# mother4.net
KiCad netlist of a schematic drawn in EAGLE
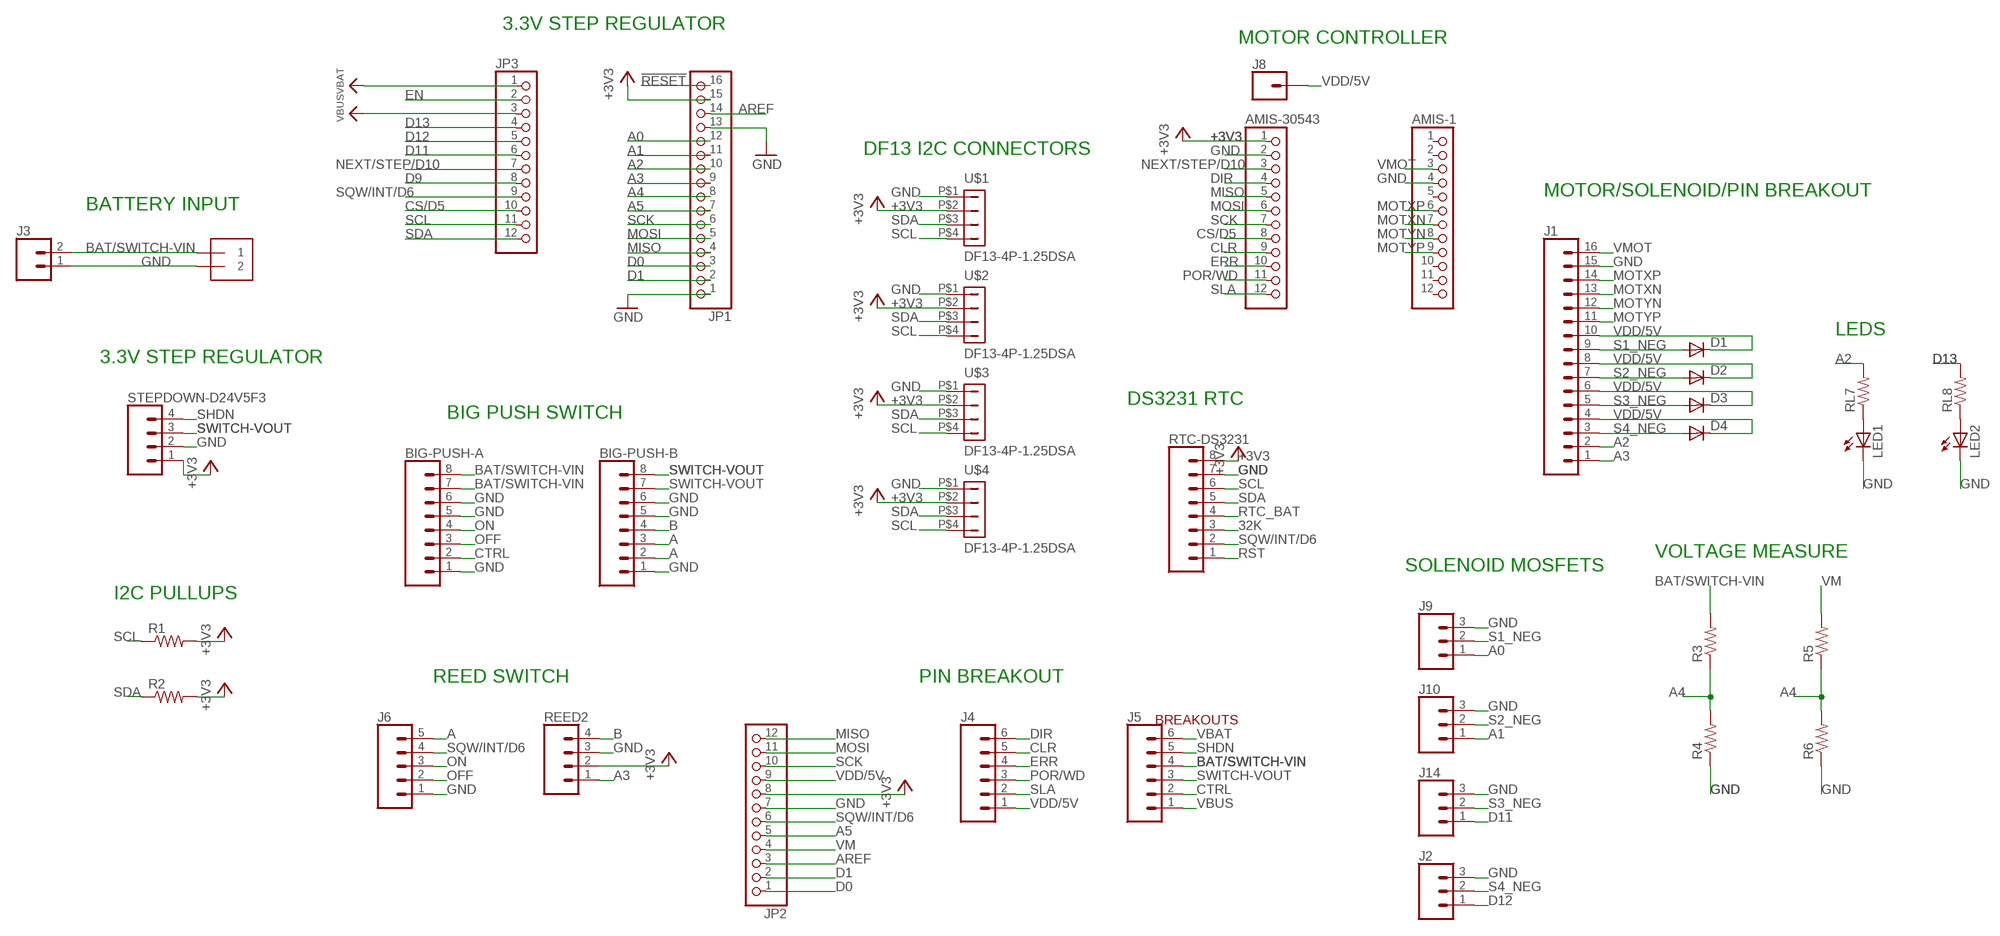
[diagram p0: schematic, sheet 1]

(export (version "E")
  (design (tool "Eeschema 10.0.6"))
  (components
    (comp (ref "AMIS-1")
      (value "PINHD-1X12-CB")
      (footprint "eagle-import:1X12-CB")
      (libsource (lib "eagle-import") (part "PINHD-1X12-CB"))
    )
    (comp (ref "AMIS-30543")
      (value "PINHD-1X12-CB")
      (footprint "eagle-import:1X12-CB")
      (libsource (lib "eagle-import") (part "PINHD-1X12-CB"))
    )
    (comp (ref "BAT")
      (value "1X2-3.5MM")
      (footprint "eagle-import:1X2-3.5MM")
      (libsource (lib "eagle-import") (part "1X2-3.5MM"))
    )
    (comp (ref "BIG-PUSH-A")
      (value "CONN_08\"")
      (footprint "eagle-import:1X08")
      (libsource (lib "eagle-import") (part "CONN_08{dblquote}"))
    )
    (comp (ref "BIG-PUSH-B")
      (value "CONN_08\"")
      (footprint "eagle-import:1X08")
      (libsource (lib "eagle-import") (part "CONN_08{dblquote}"))
    )
    (comp (ref "D1")
      (value "1N4148DO35-7")
      (footprint "eagle-import:DO35-7")
      (libsource (lib "eagle-import") (part "1N4148DO35-7"))
    )
    (comp (ref "D2")
      (value "1N4148DO35-7")
      (footprint "eagle-import:DO35-7")
      (libsource (lib "eagle-import") (part "1N4148DO35-7"))
    )
    (comp (ref "D3")
      (value "1N4148DO35-7")
      (footprint "eagle-import:DO35-7")
      (libsource (lib "eagle-import") (part "1N4148DO35-7"))
    )
    (comp (ref "D4")
      (value "1N4148DO35-7")
      (footprint "eagle-import:DO35-7")
      (libsource (lib "eagle-import") (part "1N4148DO35-7"))
    )
    (comp (ref "J1")
      (value "CONN_16")
      (footprint "eagle-import:1X16")
      (libsource (lib "eagle-import") (part "CONN_16"))
    )
    (comp (ref "J2")
      (value "CONN_03")
      (footprint "eagle-import:1X03")
      (libsource (lib "eagle-import") (part "CONN_03"))
    )
    (comp (ref "J3")
      (value "CONN_02")
      (footprint "eagle-import:1X02")
      (libsource (lib "eagle-import") (part "CONN_02"))
    )
    (comp (ref "J4")
      (value "CONN_06SILK_FEMALE_PTH")
      (footprint "eagle-import:1X06")
      (libsource (lib "eagle-import") (part "CONN_06SILK_FEMALE_PTH"))
    )
    (comp (ref "J5")
      (value "CONN_06SILK_FEMALE_PTH")
      (footprint "eagle-import:1X06")
      (libsource (lib "eagle-import") (part "CONN_06SILK_FEMALE_PTH"))
    )
    (comp (ref "J6")
      (value "CONN_05")
      (footprint "eagle-import:1X05")
      (libsource (lib "eagle-import") (part "CONN_05"))
    )
    (comp (ref "J8")
      (value "CONN_01")
      (footprint "eagle-import:1X01")
      (libsource (lib "eagle-import") (part "CONN_01"))
    )
    (comp (ref "J9")
      (value "CONN_03")
      (footprint "eagle-import:1X03")
      (libsource (lib "eagle-import") (part "CONN_03"))
    )
    (comp (ref "J10")
      (value "CONN_03")
      (footprint "eagle-import:1X03")
      (libsource (lib "eagle-import") (part "CONN_03"))
    )
    (comp (ref "J14")
      (value "CONN_03")
      (footprint "eagle-import:1X03")
      (libsource (lib "eagle-import") (part "CONN_03"))
    )
    (comp (ref "JP1")
      (value "HEADER-1X16ROUND")
      (footprint "eagle-import:1X16_ROUND")
      (libsource (lib "eagle-import") (part "HEADER-1X16ROUND"))
    )
    (comp (ref "JP2")
      (value "HEADER-1X12")
      (footprint "eagle-import:1X12_ROUND")
      (libsource (lib "eagle-import") (part "HEADER-1X12"))
    )
    (comp (ref "JP3")
      (value "HEADER-1X12")
      (footprint "eagle-import:1X12_ROUND")
      (libsource (lib "eagle-import") (part "HEADER-1X12"))
    )
    (comp (ref "LED1")
      (value "LED5MM")
      (footprint "eagle-import:LED5MM")
      (libsource (lib "eagle-import") (part "LED5MM"))
    )
    (comp (ref "LED2")
      (value "LED5MM")
      (footprint "eagle-import:LED5MM")
      (libsource (lib "eagle-import") (part "LED5MM"))
    )
    (comp (ref "R1")
      (value "R-US_0207/10")
      (footprint "eagle-import:0207_10")
      (libsource (lib "eagle-import") (part "R-US_0207/10"))
    )
    (comp (ref "R2")
      (value "R-US_0207/10")
      (footprint "eagle-import:0207_10")
      (libsource (lib "eagle-import") (part "R-US_0207/10"))
    )
    (comp (ref "R3")
      (value "R-US_0207/10")
      (footprint "eagle-import:0207_10")
      (libsource (lib "eagle-import") (part "R-US_0207/10"))
    )
    (comp (ref "R4")
      (value "R-US_0207/10")
      (footprint "eagle-import:0207_10")
      (libsource (lib "eagle-import") (part "R-US_0207/10"))
    )
    (comp (ref "R5")
      (value "R-US_0207/10")
      (footprint "eagle-import:0207_10")
      (libsource (lib "eagle-import") (part "R-US_0207/10"))
    )
    (comp (ref "R6")
      (value "R-US_0207/10")
      (footprint "eagle-import:0207_10")
      (libsource (lib "eagle-import") (part "R-US_0207/10"))
    )
    (comp (ref "REED2")
      (value "CONN_04")
      (footprint "eagle-import:1X04")
      (libsource (lib "eagle-import") (part "CONN_04"))
    )
    (comp (ref "RL7")
      (value "R-US_0207/10")
      (footprint "eagle-import:0207_10")
      (libsource (lib "eagle-import") (part "R-US_0207/10"))
    )
    (comp (ref "RL8")
      (value "R-US_0207/10")
      (footprint "eagle-import:0207_10")
      (libsource (lib "eagle-import") (part "R-US_0207/10"))
    )
    (comp (ref "RTC-DS3231")
      (value "CONN_08\"")
      (footprint "eagle-import:1X08")
      (libsource (lib "eagle-import") (part "CONN_08{dblquote}"))
    )
    (comp (ref "STEPDOWN-D24V5F3")
      (value "CONN_04")
      (footprint "eagle-import:1X04")
      (libsource (lib "eagle-import") (part "CONN_04"))
    )
    (comp (ref "U$1")
      (value "DF13-4P-1.25DSA")
      (footprint "eagle-import:DF13-4P-1.25DSA")
      (libsource (lib "eagle-import") (part "DF13-4P-1.25DSA"))
    )
    (comp (ref "U$2")
      (value "DF13-4P-1.25DSA")
      (footprint "eagle-import:DF13-4P-1.25DSA")
      (libsource (lib "eagle-import") (part "DF13-4P-1.25DSA"))
    )
    (comp (ref "U$3")
      (value "DF13-4P-1.25DSA")
      (footprint "eagle-import:DF13-4P-1.25DSA")
      (libsource (lib "eagle-import") (part "DF13-4P-1.25DSA"))
    )
    (comp (ref "U$4")
      (value "DF13-4P-1.25DSA")
      (footprint "eagle-import:DF13-4P-1.25DSA")
      (libsource (lib "eagle-import") (part "DF13-4P-1.25DSA"))
    )
  )
  (nets
    (net (code "1") (name "+3V3") (class "Default")
      (node (ref "AMIS-30543") (pin "1") (pinfunction "1_1") (pintype "passive"))
      (node (ref "JP1") (pin "15") (pinfunction "15_15") (pintype "passive"))
      (node (ref "JP2") (pin "8") (pinfunction "8_8") (pintype "passive"))
      (node (ref "R1") (pin "2") (pinfunction "2_2") (pintype "passive"))
      (node (ref "R2") (pin "2") (pinfunction "2_2") (pintype "passive"))
      (node (ref "REED2") (pin "2") (pinfunction "2_2") (pintype "passive"))
      (node (ref "RTC-DS3231") (pin "8") (pinfunction "8_8") (pintype "passive"))
      (node (ref "STEPDOWN-D24V5F3") (pin "1") (pinfunction "1_1") (pintype "passive"))
      (node (ref "U$1") (pin "P$2") (pinfunction "2_P$2") (pintype "passive"))
      (node (ref "U$2") (pin "P$2") (pinfunction "2_P$2") (pintype "passive"))
      (node (ref "U$3") (pin "P$2") (pinfunction "2_P$2") (pintype "passive"))
      (node (ref "U$4") (pin "P$2") (pinfunction "2_P$2") (pintype "passive"))
    )
    (net (code "2") (name "/32K") (class "Default")
      (node (ref "RTC-DS3231") (pin "3") (pinfunction "3_3") (pintype "passive"))
    )
    (net (code "3") (name "/A") (class "Default")
      (node (ref "BIG-PUSH-B") (pin "2") (pinfunction "2_2") (pintype "passive"))
      (node (ref "BIG-PUSH-B") (pin "3") (pinfunction "3_3") (pintype "passive"))
      (node (ref "J6") (pin "5") (pinfunction "5_5") (pintype "passive"))
    )
    (net (code "4") (name "/A0") (class "Default")
      (node (ref "J9") (pin "1") (pinfunction "1_1") (pintype "passive"))
      (node (ref "JP1") (pin "12") (pinfunction "12_12") (pintype "passive"))
    )
    (net (code "5") (name "/A1") (class "Default")
      (node (ref "J10") (pin "1") (pinfunction "1_1") (pintype "passive"))
      (node (ref "JP1") (pin "11") (pinfunction "11_11") (pintype "passive"))
    )
    (net (code "6") (name "/A2") (class "Default")
      (node (ref "J1") (pin "2") (pinfunction "2_2") (pintype "passive"))
      (node (ref "JP1") (pin "10") (pinfunction "10_10") (pintype "passive"))
      (node (ref "RL7") (pin "2") (pinfunction "2_2") (pintype "passive"))
    )
    (net (code "7") (name "/A3") (class "Default")
      (node (ref "J1") (pin "1") (pinfunction "1_1") (pintype "passive"))
      (node (ref "JP1") (pin "9") (pinfunction "9_9") (pintype "passive"))
      (node (ref "REED2") (pin "1") (pinfunction "1_1") (pintype "passive"))
    )
    (net (code "8") (name "/A4") (class "Default")
      (node (ref "JP1") (pin "8") (pinfunction "8_8") (pintype "passive"))
      (node (ref "R3") (pin "1") (pinfunction "1_1") (pintype "passive"))
      (node (ref "R4") (pin "2") (pinfunction "2_2") (pintype "passive"))
      (node (ref "R5") (pin "1") (pinfunction "1_1") (pintype "passive"))
      (node (ref "R6") (pin "2") (pinfunction "2_2") (pintype "passive"))
    )
    (net (code "9") (name "/A5") (class "Default")
      (node (ref "JP1") (pin "7") (pinfunction "7_7") (pintype "passive"))
      (node (ref "JP2") (pin "5") (pinfunction "5_5") (pintype "passive"))
    )
    (net (code "10") (name "/AREF") (class "Default")
      (node (ref "JP1") (pin "14") (pinfunction "14_14") (pintype "passive"))
      (node (ref "JP2") (pin "3") (pinfunction "3_3") (pintype "passive"))
    )
    (net (code "11") (name "/B") (class "Default")
      (node (ref "BIG-PUSH-B") (pin "4") (pinfunction "4_4") (pintype "passive"))
      (node (ref "REED2") (pin "4") (pinfunction "4_4") (pintype "passive"))
    )
    (net (code "12") (name "/BAT{slash}SWITCH-VIN") (class "Default")
      (node (ref "BAT") (pin "1") (pinfunction "1_1") (pintype "passive"))
      (node (ref "BIG-PUSH-A") (pin "7") (pinfunction "7_7") (pintype "passive"))
      (node (ref "BIG-PUSH-A") (pin "8") (pinfunction "8_8") (pintype "passive"))
      (node (ref "J3") (pin "2") (pinfunction "2_2") (pintype "passive"))
      (node (ref "J5") (pin "4") (pinfunction "4_4") (pintype "passive"))
      (node (ref "R3") (pin "2") (pinfunction "2_2") (pintype "passive"))
    )
    (net (code "13") (name "/CLR") (class "Default")
      (node (ref "AMIS-30543") (pin "9") (pinfunction "9_9") (pintype "passive"))
      (node (ref "J4") (pin "5") (pinfunction "5_5") (pintype "passive"))
    )
    (net (code "14") (name "/CS{slash}D5") (class "Default")
      (node (ref "AMIS-30543") (pin "8") (pinfunction "8_8") (pintype "passive"))
      (node (ref "JP3") (pin "10") (pinfunction "10_10") (pintype "passive"))
    )
    (net (code "15") (name "/CTRL") (class "Default")
      (node (ref "BIG-PUSH-A") (pin "2") (pinfunction "2_2") (pintype "passive"))
      (node (ref "J5") (pin "2") (pinfunction "2_2") (pintype "passive"))
    )
    (net (code "16") (name "/D0") (class "Default")
      (node (ref "JP1") (pin "3") (pinfunction "3_3") (pintype "passive"))
      (node (ref "JP2") (pin "1") (pinfunction "1_1") (pintype "passive"))
    )
    (net (code "17") (name "/D1") (class "Default")
      (node (ref "JP1") (pin "2") (pinfunction "2_2") (pintype "passive"))
      (node (ref "JP2") (pin "2") (pinfunction "2_2") (pintype "passive"))
    )
    (net (code "18") (name "/D9") (class "Default")
      (node (ref "JP3") (pin "8") (pinfunction "8_8") (pintype "passive"))
    )
    (net (code "19") (name "/D11") (class "Default")
      (node (ref "J14") (pin "1") (pinfunction "1_1") (pintype "passive"))
      (node (ref "JP3") (pin "6") (pinfunction "6_6") (pintype "passive"))
    )
    (net (code "20") (name "/D12") (class "Default")
      (node (ref "J2") (pin "1") (pinfunction "1_1") (pintype "passive"))
      (node (ref "JP3") (pin "5") (pinfunction "5_5") (pintype "passive"))
    )
    (net (code "21") (name "/D13") (class "Default")
      (node (ref "JP3") (pin "4") (pinfunction "4_4") (pintype "passive"))
      (node (ref "RL8") (pin "2") (pinfunction "2_2") (pintype "passive"))
    )
    (net (code "22") (name "/DIR") (class "Default")
      (node (ref "AMIS-30543") (pin "4") (pinfunction "4_4") (pintype "passive"))
      (node (ref "J4") (pin "6") (pinfunction "6_6") (pintype "passive"))
    )
    (net (code "23") (name "/EN") (class "Default")
      (node (ref "JP3") (pin "2") (pinfunction "2_2") (pintype "passive"))
    )
    (net (code "24") (name "/ERR") (class "Default")
      (node (ref "AMIS-30543") (pin "10") (pinfunction "10_10") (pintype "passive"))
      (node (ref "J4") (pin "4") (pinfunction "4_4") (pintype "passive"))
    )
    (net (code "25") (name "/MISO") (class "Default")
      (node (ref "AMIS-30543") (pin "5") (pinfunction "5_5") (pintype "passive"))
      (node (ref "JP1") (pin "4") (pinfunction "4_4") (pintype "passive"))
      (node (ref "JP2") (pin "12") (pinfunction "12_12") (pintype "passive"))
    )
    (net (code "26") (name "/MOSI") (class "Default")
      (node (ref "AMIS-30543") (pin "6") (pinfunction "6_6") (pintype "passive"))
      (node (ref "JP1") (pin "5") (pinfunction "5_5") (pintype "passive"))
      (node (ref "JP2") (pin "11") (pinfunction "11_11") (pintype "passive"))
    )
    (net (code "27") (name "/MOTXN") (class "Default")
      (node (ref "AMIS-1") (pin "7") (pinfunction "7_7") (pintype "passive"))
      (node (ref "J1") (pin "13") (pinfunction "13_13") (pintype "passive"))
    )
    (net (code "28") (name "/MOTXP") (class "Default")
      (node (ref "AMIS-1") (pin "6") (pinfunction "6_6") (pintype "passive"))
      (node (ref "J1") (pin "14") (pinfunction "14_14") (pintype "passive"))
    )
    (net (code "29") (name "/MOTYN") (class "Default")
      (node (ref "AMIS-1") (pin "8") (pinfunction "8_8") (pintype "passive"))
      (node (ref "J1") (pin "12") (pinfunction "12_12") (pintype "passive"))
    )
    (net (code "30") (name "/MOTYP") (class "Default")
      (node (ref "AMIS-1") (pin "9") (pinfunction "9_9") (pintype "passive"))
      (node (ref "J1") (pin "11") (pinfunction "11_11") (pintype "passive"))
    )
    (net (code "31") (name "/NEXT{slash}STEP{slash}D10") (class "Default")
      (node (ref "AMIS-30543") (pin "3") (pinfunction "3_3") (pintype "passive"))
      (node (ref "JP3") (pin "7") (pinfunction "7_7") (pintype "passive"))
    )
    (net (code "32") (name "/OFF") (class "Default")
      (node (ref "BIG-PUSH-A") (pin "3") (pinfunction "3_3") (pintype "passive"))
      (node (ref "J6") (pin "2") (pinfunction "2_2") (pintype "passive"))
    )
    (net (code "33") (name "/ON") (class "Default")
      (node (ref "BIG-PUSH-A") (pin "4") (pinfunction "4_4") (pintype "passive"))
      (node (ref "J6") (pin "3") (pinfunction "3_3") (pintype "passive"))
    )
    (net (code "34") (name "/POR{slash}WD") (class "Default")
      (node (ref "AMIS-30543") (pin "11") (pinfunction "11_11") (pintype "passive"))
      (node (ref "J4") (pin "3") (pinfunction "3_3") (pintype "passive"))
    )
    (net (code "35") (name "/RST") (class "Default")
      (node (ref "RTC-DS3231") (pin "1") (pinfunction "1_1") (pintype "passive"))
    )
    (net (code "36") (name "/RTC_BAT") (class "Default")
      (node (ref "RTC-DS3231") (pin "4") (pinfunction "4_4") (pintype "passive"))
    )
    (net (code "37") (name "/S1_NEG") (class "Default")
      (node (ref "D1") (pin "A") (pinfunction "A_A") (pintype "passive"))
      (node (ref "J1") (pin "9") (pinfunction "9_9") (pintype "passive"))
      (node (ref "J9") (pin "2") (pinfunction "2_2") (pintype "passive"))
    )
    (net (code "38") (name "/S2_NEG") (class "Default")
      (node (ref "D2") (pin "A") (pinfunction "A_A") (pintype "passive"))
      (node (ref "J1") (pin "7") (pinfunction "7_7") (pintype "passive"))
      (node (ref "J10") (pin "2") (pinfunction "2_2") (pintype "passive"))
    )
    (net (code "39") (name "/S3_NEG") (class "Default")
      (node (ref "D3") (pin "A") (pinfunction "A_A") (pintype "passive"))
      (node (ref "J1") (pin "5") (pinfunction "5_5") (pintype "passive"))
      (node (ref "J14") (pin "2") (pinfunction "2_2") (pintype "passive"))
    )
    (net (code "40") (name "/S4_NEG") (class "Default")
      (node (ref "D4") (pin "A") (pinfunction "A_A") (pintype "passive"))
      (node (ref "J1") (pin "3") (pinfunction "3_3") (pintype "passive"))
      (node (ref "J2") (pin "2") (pinfunction "2_2") (pintype "passive"))
    )
    (net (code "41") (name "/SCK") (class "Default")
      (node (ref "AMIS-30543") (pin "7") (pinfunction "7_7") (pintype "passive"))
      (node (ref "JP1") (pin "6") (pinfunction "6_6") (pintype "passive"))
      (node (ref "JP2") (pin "10") (pinfunction "10_10") (pintype "passive"))
    )
    (net (code "42") (name "/SCL") (class "Default")
      (node (ref "JP3") (pin "11") (pinfunction "11_11") (pintype "passive"))
      (node (ref "R1") (pin "1") (pinfunction "1_1") (pintype "passive"))
      (node (ref "RTC-DS3231") (pin "6") (pinfunction "6_6") (pintype "passive"))
      (node (ref "U$1") (pin "P$4") (pinfunction "4_P$4") (pintype "passive"))
      (node (ref "U$2") (pin "P$4") (pinfunction "4_P$4") (pintype "passive"))
      (node (ref "U$3") (pin "P$4") (pinfunction "4_P$4") (pintype "passive"))
      (node (ref "U$4") (pin "P$4") (pinfunction "4_P$4") (pintype "passive"))
    )
    (net (code "43") (name "/SDA") (class "Default")
      (node (ref "JP3") (pin "12") (pinfunction "12_12") (pintype "passive"))
      (node (ref "R2") (pin "1") (pinfunction "1_1") (pintype "passive"))
      (node (ref "RTC-DS3231") (pin "5") (pinfunction "5_5") (pintype "passive"))
      (node (ref "U$1") (pin "P$3") (pinfunction "3_P$3") (pintype "passive"))
      (node (ref "U$2") (pin "P$3") (pinfunction "3_P$3") (pintype "passive"))
      (node (ref "U$3") (pin "P$3") (pinfunction "3_P$3") (pintype "passive"))
      (node (ref "U$4") (pin "P$3") (pinfunction "3_P$3") (pintype "passive"))
    )
    (net (code "44") (name "/SHDN") (class "Default")
      (node (ref "J5") (pin "5") (pinfunction "5_5") (pintype "passive"))
      (node (ref "STEPDOWN-D24V5F3") (pin "4") (pinfunction "4_4") (pintype "passive"))
    )
    (net (code "45") (name "/SLA") (class "Default")
      (node (ref "AMIS-30543") (pin "12") (pinfunction "12_12") (pintype "passive"))
      (node (ref "J4") (pin "2") (pinfunction "2_2") (pintype "passive"))
    )
    (net (code "46") (name "/SQW{slash}INT{slash}D6") (class "Default")
      (node (ref "J6") (pin "4") (pinfunction "4_4") (pintype "passive"))
      (node (ref "JP2") (pin "6") (pinfunction "6_6") (pintype "passive"))
      (node (ref "JP3") (pin "9") (pinfunction "9_9") (pintype "passive"))
      (node (ref "RTC-DS3231") (pin "2") (pinfunction "2_2") (pintype "passive"))
    )
    (net (code "47") (name "/SWITCH-VOUT") (class "Default")
      (node (ref "BIG-PUSH-B") (pin "7") (pinfunction "7_7") (pintype "passive"))
      (node (ref "BIG-PUSH-B") (pin "8") (pinfunction "8_8") (pintype "passive"))
      (node (ref "J5") (pin "3") (pinfunction "3_3") (pintype "passive"))
      (node (ref "STEPDOWN-D24V5F3") (pin "3") (pinfunction "3_3") (pintype "passive"))
    )
    (net (code "48") (name "/VDD{slash}5V") (class "Default")
      (node (ref "D1") (pin "C") (pinfunction "C_C") (pintype "passive"))
      (node (ref "D2") (pin "C") (pinfunction "C_C") (pintype "passive"))
      (node (ref "D3") (pin "C") (pinfunction "C_C") (pintype "passive"))
      (node (ref "D4") (pin "C") (pinfunction "C_C") (pintype "passive"))
      (node (ref "J1") (pin "10") (pinfunction "10_10") (pintype "passive"))
      (node (ref "J1") (pin "4") (pinfunction "4_4") (pintype "passive"))
      (node (ref "J1") (pin "6") (pinfunction "6_6") (pintype "passive"))
      (node (ref "J1") (pin "8") (pinfunction "8_8") (pintype "passive"))
      (node (ref "J4") (pin "1") (pinfunction "1_1") (pintype "passive"))
      (node (ref "J8") (pin "1") (pinfunction "1_1") (pintype "passive"))
      (node (ref "JP2") (pin "9") (pinfunction "9_9") (pintype "passive"))
    )
    (net (code "49") (name "/VM") (class "Default")
      (node (ref "JP2") (pin "4") (pinfunction "4_4") (pintype "passive"))
      (node (ref "R5") (pin "2") (pinfunction "2_2") (pintype "passive"))
    )
    (net (code "50") (name "/VMOT") (class "Default")
      (node (ref "AMIS-1") (pin "3") (pinfunction "3_3") (pintype "passive"))
      (node (ref "J1") (pin "16") (pinfunction "16_16") (pintype "passive"))
    )
    (net (code "51") (name "/~{RESET}") (class "Default")
      (node (ref "JP1") (pin "16") (pinfunction "16_16") (pintype "passive"))
    )
    (net (code "52") (name "GND") (class "Default")
      (node (ref "AMIS-1") (pin "4") (pinfunction "4_4") (pintype "passive"))
      (node (ref "AMIS-30543") (pin "2") (pinfunction "2_2") (pintype "passive"))
      (node (ref "BAT") (pin "2") (pinfunction "2_2") (pintype "passive"))
      (node (ref "BIG-PUSH-A") (pin "1") (pinfunction "1_1") (pintype "passive"))
      (node (ref "BIG-PUSH-A") (pin "5") (pinfunction "5_5") (pintype "passive"))
      (node (ref "BIG-PUSH-A") (pin "6") (pinfunction "6_6") (pintype "passive"))
      (node (ref "BIG-PUSH-B") (pin "1") (pinfunction "1_1") (pintype "passive"))
      (node (ref "BIG-PUSH-B") (pin "5") (pinfunction "5_5") (pintype "passive"))
      (node (ref "BIG-PUSH-B") (pin "6") (pinfunction "6_6") (pintype "passive"))
      (node (ref "J1") (pin "15") (pinfunction "15_15") (pintype "passive"))
      (node (ref "J10") (pin "3") (pinfunction "3_3") (pintype "passive"))
      (node (ref "J14") (pin "3") (pinfunction "3_3") (pintype "passive"))
      (node (ref "J2") (pin "3") (pinfunction "3_3") (pintype "passive"))
      (node (ref "J3") (pin "1") (pinfunction "1_1") (pintype "passive"))
      (node (ref "J6") (pin "1") (pinfunction "1_1") (pintype "passive"))
      (node (ref "J9") (pin "3") (pinfunction "3_3") (pintype "passive"))
      (node (ref "JP1") (pin "1") (pinfunction "1_1") (pintype "passive"))
      (node (ref "JP1") (pin "13") (pinfunction "13_13") (pintype "passive"))
      (node (ref "JP2") (pin "7") (pinfunction "7_7") (pintype "passive"))
      (node (ref "LED1") (pin "K") (pinfunction "C_K") (pintype "passive"))
      (node (ref "LED2") (pin "K") (pinfunction "C_K") (pintype "passive"))
      (node (ref "R4") (pin "1") (pinfunction "1_1") (pintype "passive"))
      (node (ref "R6") (pin "1") (pinfunction "1_1") (pintype "passive"))
      (node (ref "REED2") (pin "3") (pinfunction "3_3") (pintype "passive"))
      (node (ref "RTC-DS3231") (pin "7") (pinfunction "7_7") (pintype "passive"))
      (node (ref "STEPDOWN-D24V5F3") (pin "2") (pinfunction "2_2") (pintype "passive"))
      (node (ref "U$1") (pin "P$1") (pinfunction "1_P$1") (pintype "passive"))
      (node (ref "U$2") (pin "P$1") (pinfunction "1_P$1") (pintype "passive"))
      (node (ref "U$3") (pin "P$1") (pinfunction "1_P$1") (pintype "passive"))
      (node (ref "U$4") (pin "P$1") (pinfunction "1_P$1") (pintype "passive"))
    )
    (net (code "53") (name "Net-(LED1-PadA)") (class "Default")
      (node (ref "LED1") (pin "A") (pinfunction "A_A") (pintype "passive"))
      (node (ref "RL7") (pin "1") (pinfunction "1_1") (pintype "passive"))
    )
    (net (code "54") (name "Net-(LED2-PadA)") (class "Default")
      (node (ref "LED2") (pin "A") (pinfunction "A_A") (pintype "passive"))
      (node (ref "RL8") (pin "1") (pinfunction "1_1") (pintype "passive"))
    )
    (net (code "55") (name "VBAT") (class "Default")
      (node (ref "J5") (pin "6") (pinfunction "6_6") (pintype "passive"))
      (node (ref "JP3") (pin "1") (pinfunction "1_1") (pintype "passive"))
    )
    (net (code "56") (name "VBUS") (class "Default")
      (node (ref "J5") (pin "1") (pinfunction "1_1") (pintype "passive"))
      (node (ref "JP3") (pin "3") (pinfunction "3_3") (pintype "passive"))
    )
    (net (code "57") (name "unconnected-(AMIS-1-Pad1)") (class "Default")
      (node (ref "AMIS-1") (pin "1") (pinfunction "1_1") (pintype "passive"))
    )
    (net (code "58") (name "unconnected-(AMIS-1-Pad2)") (class "Default")
      (node (ref "AMIS-1") (pin "2") (pinfunction "2_2") (pintype "passive"))
    )
    (net (code "59") (name "unconnected-(AMIS-1-Pad5)") (class "Default")
      (node (ref "AMIS-1") (pin "5") (pinfunction "5_5") (pintype "passive"))
    )
    (net (code "60") (name "unconnected-(AMIS-1-Pad10)") (class "Default")
      (node (ref "AMIS-1") (pin "10") (pinfunction "10_10") (pintype "passive"))
    )
    (net (code "61") (name "unconnected-(AMIS-1-Pad11)") (class "Default")
      (node (ref "AMIS-1") (pin "11") (pinfunction "11_11") (pintype "passive"))
    )
    (net (code "62") (name "unconnected-(AMIS-1-Pad12)") (class "Default")
      (node (ref "AMIS-1") (pin "12") (pinfunction "12_12") (pintype "passive"))
    )
  )
)
